# Active_Clamp.net
KiCad netlist of a schematic drawn in Altium Designer
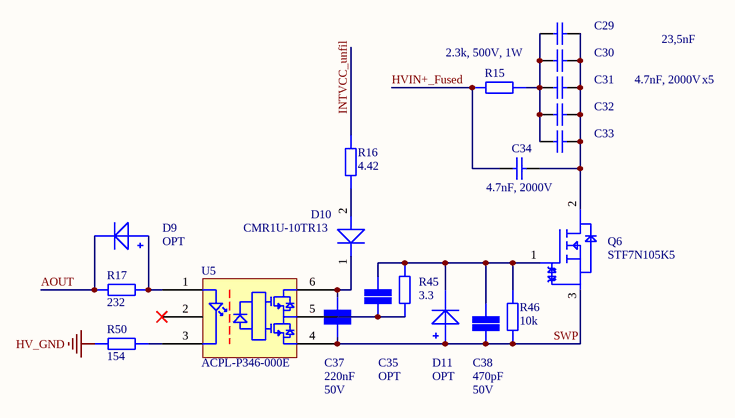
[diagram p0: Active_Clamp.SchDoc]

(export (version "E")
  (design (tool "Eeschema 10.0.6"))
  (components
    (comp (ref "C29")
      (value "4.7nF, 2000V")
      (footprint "WCAP-CSMH_1812_H2")
      (description "WCAP-CSMH Multilayer Ceramic Chip Capacitor, size 1812, X7R Class II, 4.7nF, 2000V")
      (fields
        (field (name "MANUFACTURER PART NUMBER") "885342211008")
        (field (name "MANUFACTURER") "Wurth Elektronik")
      )
      (libsource (lib "Altium_WCAP-CSMH (rev20a)") (part "885342211008"))
    )
    (comp (ref "C30")
      (value "4.7nF, 2000V")
      (footprint "WCAP-CSMH_1812_H2")
      (description "WCAP-CSMH Multilayer Ceramic Chip Capacitor, size 1812, X7R Class II, 4.7nF, 2000V")
      (fields
        (field (name "MANUFACTURER PART NUMBER") "885342211008")
        (field (name "MANUFACTURER") "Wurth Elektronik")
      )
      (libsource (lib "Altium_WCAP-CSMH (rev20a)") (part "885342211008"))
    )
    (comp (ref "C31")
      (value "4.7nF, 2000V")
      (footprint "WCAP-CSMH_1812_H2")
      (description "WCAP-CSMH Multilayer Ceramic Chip Capacitor, size 1812, X7R Class II, 4.7nF, 2000V")
      (fields
        (field (name "MANUFACTURER PART NUMBER") "885342211008")
        (field (name "MANUFACTURER") "Wurth Elektronik")
      )
      (libsource (lib "Altium_WCAP-CSMH (rev20a)") (part "885342211008"))
    )
    (comp (ref "C32")
      (value "4.7nF, 2000V")
      (footprint "WCAP-CSMH_1812_H2")
      (description "WCAP-CSMH Multilayer Ceramic Chip Capacitor, size 1812, X7R Class II, 4.7nF, 2000V")
      (fields
        (field (name "MANUFACTURER PART NUMBER") "885342211008")
        (field (name "MANUFACTURER") "Wurth Elektronik")
      )
      (libsource (lib "Altium_WCAP-CSMH (rev20a)") (part "885342211008"))
    )
    (comp (ref "C33")
      (value "4.7nF, 2000V")
      (footprint "WCAP-CSMH_1812_H2")
      (description "WCAP-CSMH Multilayer Ceramic Chip Capacitor, size 1812, X7R Class II, 4.7nF, 2000V")
      (fields
        (field (name "MANUFACTURER PART NUMBER") "885342211008")
        (field (name "MANUFACTURER") "Wurth Elektronik")
      )
      (libsource (lib "Altium_WCAP-CSMH (rev20a)") (part "885342211008"))
    )
    (comp (ref "C34")
      (value "4.7nF, 2000V")
      (footprint "WCAP-CSMH_1812_H2")
      (description "WCAP-CSMH Multilayer Ceramic Chip Capacitor, size 1812, X7R Class II, 4.7nF, 2000V")
      (fields
        (field (name "MANUFACTURER PART NUMBER") "885342211008")
        (field (name "MANUFACTURER") "Wurth Elektronik")
      )
      (libsource (lib "Altium_WCAP-CSMH (rev20a)") (part "885342211008"))
    )
    (comp (ref "C35")
      (value "OPT")
      (footprint "CAP 1206/3216")
      (description "Capacitor with multiple Footprints")
      (fields (field (name "Comment") "SMD Capacitor"))
      (libsource (lib "Standardbauteile") (part "SMD Capacitor"))
    )
    (comp (ref "C37")
      (value "220nF")
      (footprint "CAP 1206/3216")
      (description "Capacitor with multiple Footprints")
      (fields (field (name "VOLTAGE") "50V") (field (name "Comment") "SMD Capacitor"))
      (libsource (lib "Standardbauteile") (part "SMD Capacitor"))
    )
    (comp (ref "C38")
      (value "470pF")
      (footprint "CAP 1206/3216")
      (description "Capacitor with multiple Footprints")
      (fields (field (name "VOLTAGE") "50V") (field (name "Comment") "SMD Capacitor"))
      (libsource (lib "Standardbauteile") (part "SMD Capacitor"))
    )
    (comp (ref "D9")
      (value "OPT")
      (footprint "DIOM2715X18N")
      (libsource (lib "Integrated_LibraryLukas_New") (part "BAT46WH"))
    )
    (comp (ref "D10")
      (value "CMR1U-10TR13")
      (footprint "DIOC4536X24L CMR1U-10")
      (description "Silicon Ultra Fast Recovery Rectifier 1000V 30A 2-Pin SMB Surface Mount T/R")
      (fields (field (name "MANUFACTURER") "Central Semiconductor"))
      (libsource (lib "Integrated_LibraryLukas_New") (part "CMR1U-10TR13"))
    )
    (comp (ref "D11")
      (value "OPT")
      (footprint "DIOM2715X18N")
      (libsource (lib "Integrated_LibraryLukas_New") (part "BAT46WH"))
    )
    (comp (ref "Q6")
      (value "STF7N105K5")
      (footprint "TO-220-3")
      (description "N-channel 1050 V, 1.4 Ohm typ., 4 A MDmesh K5 Power MOSFETs in TO-220FP package")
      (fields (field (name "MANUFACTURER") "STMicroelectronics"))
      (libsource (lib "Integrated_LibraryLukas_New") (part "STF7N105K5"))
    )
    (comp (ref "R15")
      (value "2.3k, 500V, 1W")
      (footprint "STACKPOLE CSRN2512")
      (description "Resistor with multiple footprints")
      (fields (field (name "Comment") "CRCW25122K20FKEG"))
      (libsource (lib "Standardbauteile") (part "SMD Resistor"))
    )
    (comp (ref "R16")
      (value "4.42")
      (footprint "STACKPOLE CSR0603")
      (description "Resistor with multiple footprints")
      (fields (field (name "Comment") "SMD Resistor"))
      (libsource (lib "Standardbauteile") (part "SMD Resistor"))
    )
    (comp (ref "R17")
      (value "232")
      (footprint "STACKPOLE CSR1206")
      (description "Resistor with multiple footprints")
      (fields (field (name "Comment") "SMD Resistor"))
      (libsource (lib "Standardbauteile") (part "SMD Resistor"))
    )
    (comp (ref "R45")
      (value "3.3")
      (footprint "STACKPOLE CSR0603")
      (description "Resistor with multiple footprints")
      (fields (field (name "Comment") "SMD Resistor"))
      (libsource (lib "Standardbauteile") (part "SMD Resistor"))
    )
    (comp (ref "R46")
      (value "10k")
      (footprint "STACKPOLE CSR0603")
      (description "Resistor with multiple footprints")
      (fields (field (name "Comment") "SMD Resistor"))
      (libsource (lib "Standardbauteile") (part "SMD Resistor"))
    )
    (comp (ref "R50")
      (value "154")
      (footprint "STACKPOLE CSR1206")
      (description "Resistor with multiple footprints")
      (fields (field (name "Comment") "SMD Resistor"))
      (libsource (lib "Standardbauteile") (part "SMD Resistor"))
    )
    (comp (ref "U5")
      (value "ACPL-P346-000E")
      (footprint "SOP-6 Stretched")
      (description "Logic IC Output Optocoupler, 1-Element, 3750V Isolation")
      (fields (field (name "MANUFACTURER") "Broadcom Avago"))
      (libsource (lib "Integrated_LibraryLukas_New") (part "ACPL-P346-000E"))
    )
  )
  (nets
    (net (code "1") (name "/AOUT") (class "Default")
      (node (ref "D9") (pin "2") (pintype "passive"))
      (node (ref "R17") (pin "1") (pinfunction "1_1") (pintype "passive"))
    )
    (net (code "2") (name "/HVIN+_Fused") (class "Default")
      (node (ref "C34") (pin "1") (pinfunction "1_1") (pintype "passive"))
      (node (ref "R15") (pin "2") (pinfunction "2_2") (pintype "passive"))
    )
    (net (code "3") (name "/INTVCC_unfil") (class "Default")
      (node (ref "R16") (pin "2") (pinfunction "2_2") (pintype "passive"))
    )
    (net (code "4") (name "/SWP") (class "Default")
      (node (ref "C37") (pin "2") (pinfunction "2_2") (pintype "passive"))
      (node (ref "C38") (pin "2") (pinfunction "2_2") (pintype "passive"))
      (node (ref "D11") (pin "1") (pintype "passive"))
      (node (ref "Q6") (pin "3") (pintype "passive"))
      (node (ref "R46") (pin "1") (pinfunction "1_1") (pintype "passive"))
      (node (ref "U5") (pin "4") (pintype "passive"))
    )
    (net (code "5") (name "HV_GND") (class "Default")
      (node (ref "R50") (pin "1") (pinfunction "1_1") (pintype "passive"))
    )
    (net (code "6") (name "Net-(C29-Pad1)") (class "Default")
      (node (ref "C29") (pin "1") (pinfunction "1_1") (pintype "passive"))
      (node (ref "C30") (pin "1") (pinfunction "1_1") (pintype "passive"))
      (node (ref "C31") (pin "1") (pinfunction "1_1") (pintype "passive"))
      (node (ref "C32") (pin "1") (pinfunction "1_1") (pintype "passive"))
      (node (ref "C33") (pin "1") (pinfunction "1_1") (pintype "passive"))
      (node (ref "R15") (pin "1") (pinfunction "1_1") (pintype "passive"))
    )
    (net (code "7") (name "Net-(C29-Pad2)") (class "Default")
      (node (ref "C29") (pin "2") (pinfunction "2_2") (pintype "passive"))
      (node (ref "C30") (pin "2") (pinfunction "2_2") (pintype "passive"))
      (node (ref "C31") (pin "2") (pinfunction "2_2") (pintype "passive"))
      (node (ref "C32") (pin "2") (pinfunction "2_2") (pintype "passive"))
      (node (ref "C33") (pin "2") (pinfunction "2_2") (pintype "passive"))
      (node (ref "C34") (pin "2") (pinfunction "2_2") (pintype "passive"))
      (node (ref "Q6") (pin "2") (pintype "passive"))
    )
    (net (code "8") (name "Net-(C35-Pad1)") (class "Default")
      (node (ref "C35") (pin "1") (pinfunction "1_1") (pintype "passive"))
      (node (ref "C38") (pin "1") (pinfunction "1_1") (pintype "passive"))
      (node (ref "D11") (pin "2") (pintype "passive"))
      (node (ref "Q6") (pin "1") (pintype "passive"))
      (node (ref "R45") (pin "2") (pinfunction "2_2") (pintype "passive"))
      (node (ref "R46") (pin "2") (pinfunction "2_2") (pintype "passive"))
    )
    (net (code "9") (name "Net-(C35-Pad2)") (class "Default")
      (node (ref "C35") (pin "2") (pinfunction "2_2") (pintype "passive"))
      (node (ref "R45") (pin "1") (pinfunction "1_1") (pintype "passive"))
      (node (ref "U5") (pin "5") (pintype "passive"))
    )
    (net (code "10") (name "Net-(C37-Pad1)") (class "Default")
      (node (ref "C37") (pin "1") (pinfunction "1_1") (pintype "passive"))
      (node (ref "D10") (pin "1") (pintype "passive"))
      (node (ref "U5") (pin "6") (pintype "passive"))
    )
    (net (code "11") (name "Net-(D9-Pad1)") (class "Default")
      (node (ref "D9") (pin "1") (pintype "passive"))
      (node (ref "R17") (pin "2") (pinfunction "2_2") (pintype "passive"))
      (node (ref "U5") (pin "1") (pintype "passive"))
    )
    (net (code "12") (name "Net-(D10-Pad2)") (class "Default")
      (node (ref "D10") (pin "2") (pintype "passive"))
      (node (ref "R16") (pin "1") (pinfunction "1_1") (pintype "passive"))
    )
    (net (code "13") (name "Net-(R50-Pad2)") (class "Default")
      (node (ref "R50") (pin "2") (pinfunction "2_2") (pintype "passive"))
      (node (ref "U5") (pin "3") (pintype "passive"))
    )
    (net (code "14") (name "unconnected-(U5-Pad2)") (class "Default")
      (node (ref "U5") (pin "2") (pintype "passive+no_connect"))
    )
  )
)
